# JO.net
KiCad netlist of a schematic drawn in Altium Designer
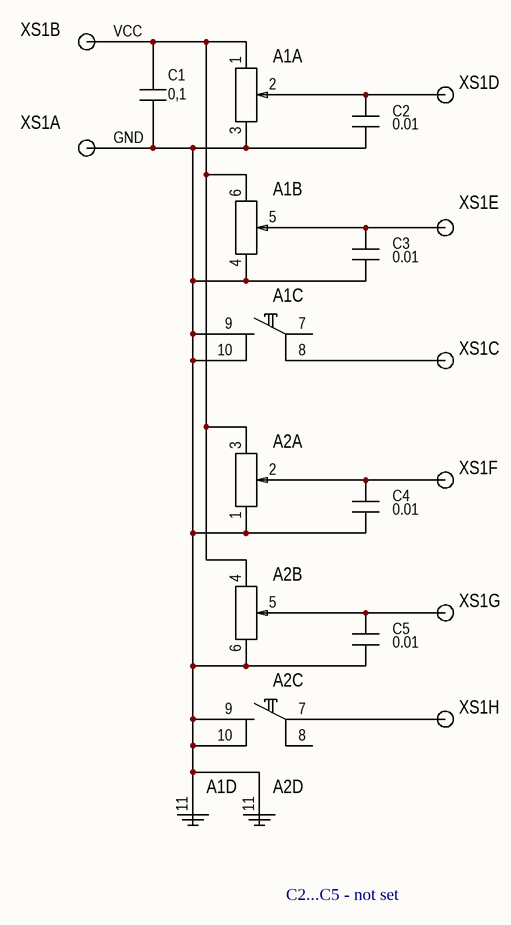
[diagram p0: JO.SchDoc]

(export (version "E")
  (design (tool "Eeschema 10.0.6"))
  (components
    (comp (ref "A1") (value "Kalih") (footprint "Kalih") (libsource (lib "Kalih") (part "Kalih")))
    (comp (ref "A2") (value "Kalih") (footprint "Kalih") (libsource (lib "Kalih") (part "Kalih")))
    (comp (ref "C1")
      (value "Cap_SMD0805")
      (footprint "cap_0805")
      (fields (field (name "ЁМКОСТЬ") "0,1"))
      (libsource (lib "Kalih") (part "Cap_SMD0805"))
    )
    (comp (ref "C2")
      (value "Cap_SMD0805")
      (footprint "cap_0805")
      (fields (field (name "ЁМКОСТЬ") "0.01"))
      (libsource (lib "Kalih") (part "Cap_SMD0805"))
    )
    (comp (ref "C3")
      (value "Cap_SMD0805")
      (footprint "cap_0805")
      (fields (field (name "ЁМКОСТЬ") "0.01"))
      (libsource (lib "Kalih") (part "Cap_SMD0805"))
    )
    (comp (ref "C4")
      (value "Cap_SMD0805")
      (footprint "cap_0805")
      (fields (field (name "ЁМКОСТЬ") "0.01"))
      (libsource (lib "Kalih") (part "Cap_SMD0805"))
    )
    (comp (ref "C5")
      (value "Cap_SMD0805")
      (footprint "cap_0805")
      (fields (field (name "ЁМКОСТЬ") "0.01"))
      (libsource (lib "Kalih") (part "Cap_SMD0805"))
    )
    (comp (ref "XS1") (value "XS8") (footprint "8H_2.5mm") (libsource (lib "Kalih") (part "XS8")))
  )
  (nets
    (net (code "1") (name "/GND") (class "Default")
      (node (ref "A1") (pin "10") (pinfunction "10_10") (pintype "passive"))
      (node (ref "A1") (pin "11") (pinfunction "11_11") (pintype "passive"))
      (node (ref "A1") (pin "3") (pinfunction "3_3") (pintype "passive"))
      (node (ref "A1") (pin "4") (pinfunction "4_4") (pintype "passive"))
      (node (ref "A1") (pin "9") (pinfunction "9_9") (pintype "passive"))
      (node (ref "A2") (pin "1") (pinfunction "1_1") (pintype "passive"))
      (node (ref "A2") (pin "10") (pinfunction "10_10") (pintype "passive"))
      (node (ref "A2") (pin "11") (pinfunction "11_11") (pintype "passive"))
      (node (ref "A2") (pin "6") (pinfunction "6_6") (pintype "passive"))
      (node (ref "A2") (pin "9") (pinfunction "9_9") (pintype "passive"))
      (node (ref "C1") (pin "1") (pinfunction "1_1") (pintype "passive"))
      (node (ref "C2") (pin "1") (pinfunction "1_1") (pintype "passive"))
      (node (ref "C3") (pin "1") (pinfunction "1_1") (pintype "passive"))
      (node (ref "C4") (pin "1") (pinfunction "1_1") (pintype "passive"))
      (node (ref "C5") (pin "1") (pinfunction "1_1") (pintype "passive"))
      (node (ref "XS1") (pin "1") (pinfunction "1_1") (pintype "passive"))
    )
    (net (code "2") (name "/VCC") (class "Default")
      (node (ref "A1") (pin "1") (pinfunction "1_1") (pintype "passive"))
      (node (ref "A1") (pin "6") (pinfunction "6_6") (pintype "passive"))
      (node (ref "A2") (pin "3") (pinfunction "3_3") (pintype "passive"))
      (node (ref "A2") (pin "4") (pinfunction "4_4") (pintype "passive"))
      (node (ref "C1") (pin "2") (pinfunction "2_2") (pintype "passive"))
      (node (ref "XS1") (pin "2") (pinfunction "2_2") (pintype "passive"))
    )
    (net (code "3") (name "Net-(A1-Pad2)") (class "Default")
      (node (ref "A1") (pin "2") (pinfunction "2_2") (pintype "passive"))
      (node (ref "C2") (pin "2") (pinfunction "2_2") (pintype "passive"))
      (node (ref "XS1") (pin "4") (pinfunction "4_4") (pintype "passive"))
    )
    (net (code "4") (name "Net-(A1-Pad5)") (class "Default")
      (node (ref "A1") (pin "5") (pinfunction "5_5") (pintype "passive"))
      (node (ref "C3") (pin "2") (pinfunction "2_2") (pintype "passive"))
      (node (ref "XS1") (pin "5") (pinfunction "5_5") (pintype "passive"))
    )
    (net (code "5") (name "Net-(A1-Pad8)") (class "Default")
      (node (ref "A1") (pin "8") (pinfunction "8_8") (pintype "passive"))
      (node (ref "XS1") (pin "3") (pinfunction "3_3") (pintype "passive"))
    )
    (net (code "6") (name "Net-(A2-Pad2)") (class "Default")
      (node (ref "A2") (pin "2") (pinfunction "2_2") (pintype "passive"))
      (node (ref "C4") (pin "2") (pinfunction "2_2") (pintype "passive"))
      (node (ref "XS1") (pin "6") (pinfunction "6_6") (pintype "passive"))
    )
    (net (code "7") (name "Net-(A2-Pad5)") (class "Default")
      (node (ref "A2") (pin "5") (pinfunction "5_5") (pintype "passive"))
      (node (ref "C5") (pin "2") (pinfunction "2_2") (pintype "passive"))
      (node (ref "XS1") (pin "7") (pinfunction "7_7") (pintype "passive"))
    )
    (net (code "8") (name "Net-(A2-Pad7)") (class "Default")
      (node (ref "A2") (pin "7") (pinfunction "7_7") (pintype "passive"))
      (node (ref "XS1") (pin "8") (pinfunction "8_8") (pintype "passive"))
    )
    (net (code "9") (name "unconnected-(A1-Pad7)") (class "Default")
      (node (ref "A1") (pin "7") (pinfunction "7_7") (pintype "passive"))
    )
    (net (code "10") (name "unconnected-(A2-Pad8)") (class "Default")
      (node (ref "A2") (pin "8") (pinfunction "8_8") (pintype "passive"))
    )
  )
)
